# KeypadCapacitive.net
KiCad netlist of a schematic drawn in Altium Designer
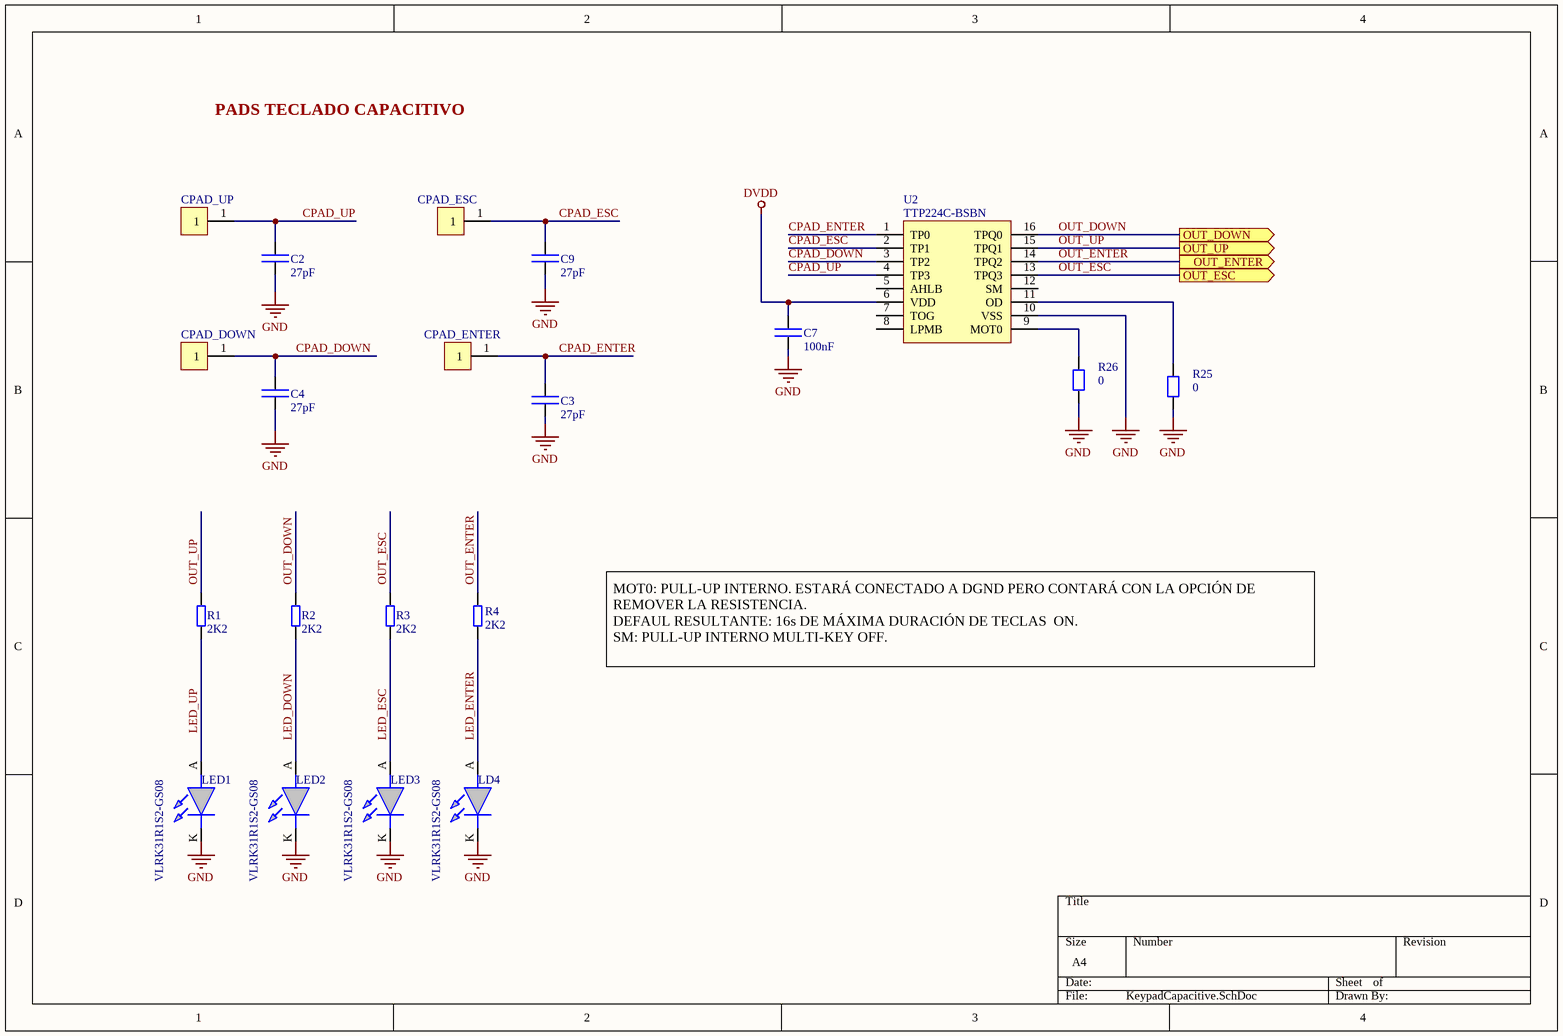
[diagram p0: KeypadCapacitive.SchDoc]

(export (version "E")
  (design (tool "Eeschema 10.0.6"))
  (components
    (comp (ref "C2")
      (value "27pF")
      (footprint "CAP_SM0603_YAGEOCC2_N")
      (description "CAP 27pF SM0603 NPO 50V YAGEO CC2")
      (fields
        (field (name "MANUFACTURER") "Yageo")
        (field (name "MANUFACTURER PART NUMBER") "CC0603JRNPO9BN270")
      )
      (libsource (lib "yageo") (part "CC0603JRNPO9BN270"))
    )
    (comp (ref "C3")
      (value "27pF")
      (footprint "CAP_SM0603_YAGEOCC2_N")
      (description "CAP 27pF SM0603 NPO 50V YAGEO CC2")
      (fields
        (field (name "MANUFACTURER") "Yageo")
        (field (name "MANUFACTURER PART NUMBER") "CC0603JRNPO9BN270")
      )
      (libsource (lib "yageo") (part "CC0603JRNPO9BN270"))
    )
    (comp (ref "C4")
      (value "27pF")
      (footprint "CAP_SM0603_YAGEOCC2_N")
      (description "CAP 27pF SM0603 NPO 50V YAGEO CC2")
      (fields
        (field (name "MANUFACTURER") "Yageo")
        (field (name "MANUFACTURER PART NUMBER") "CC0603JRNPO9BN270")
      )
      (libsource (lib "yageo") (part "CC0603JRNPO9BN270"))
    )
    (comp (ref "C7")
      (value "100nF")
      (footprint "CAP_SM0603_YAGEOCC2_N")
      (description "CAP 100nF SM0603 X7R 50V YAGEO CC2")
      (fields
        (field (name "MANUFACTURER") "Yageo")
        (field (name "MANUFACTURER PART NUMBER") "CC0603KRX7R9BB104")
      )
      (libsource (lib "yageo") (part "CC0603KRX7R9BB104"))
    )
    (comp (ref "C9")
      (value "27pF")
      (footprint "CAP_SM0603_YAGEOCC2_N")
      (description "CAP 27pF SM0603 NPO 50V YAGEO CC2")
      (fields
        (field (name "MANUFACTURER") "Yageo")
        (field (name "MANUFACTURER PART NUMBER") "CC0603JRNPO9BN270")
      )
      (libsource (lib "yageo") (part "CC0603JRNPO9BN270"))
    )
    (comp (ref "CPAD_DOWN")
      (value "DOWN")
      (footprint "CAPACITIVE_PAD_12MM")
      (fields (field (name "CHN-MANUFACTURER PARTNUMBER") "H146"))
      (libsource (lib "flowmeet") (part "CAPACITIVE_PAD_12MM"))
    )
    (comp (ref "CPAD_ENTER")
      (value "ENTER")
      (footprint "CAPACITIVE_PAD_12MM")
      (fields (field (name "CHN-MANUFACTURER PARTNUMBER") "H146"))
      (libsource (lib "flowmeet") (part "CAPACITIVE_PAD_12MM"))
    )
    (comp (ref "CPAD_ESC")
      (value "ESC")
      (footprint "CAPACITIVE_PAD_12MM")
      (fields (field (name "CHN-MANUFACTURER PARTNUMBER") "H146"))
      (libsource (lib "flowmeet") (part "CAPACITIVE_PAD_12MM"))
    )
    (comp (ref "CPAD_UP")
      (value "UP")
      (footprint "CAPACITIVE_PAD_12MM")
      (fields (field (name "CHN-MANUFACTURER PARTNUMBER") "H146"))
      (libsource (lib "flowmeet") (part "CAPACITIVE_PAD_12MM"))
    )
    (comp (ref "LD4")
      (value "VLRK31R1S2-GS08")
      (footprint "VLRK31R1S2GS08")
      (description "Red 630nm LED Indication - Discrete 2.1V 2-SMD, Z-Bend")
      (fields (field (name "MANUFACTURER") "Vishay"))
      (libsource (lib "flowmeet") (part "VLRK31R1S2-GS08"))
    )
    (comp (ref "LED1")
      (value "VLRK31R1S2-GS08")
      (footprint "VLRK31R1S2GS08")
      (description "Red 630nm LED Indication - Discrete 2.1V 2-SMD, Z-Bend")
      (fields (field (name "MANUFACTURER") "Vishay"))
      (libsource (lib "flowmeet") (part "VLRK31R1S2-GS08"))
    )
    (comp (ref "LED2")
      (value "VLRK31R1S2-GS08")
      (footprint "VLRK31R1S2GS08")
      (description "Red 630nm LED Indication - Discrete 2.1V 2-SMD, Z-Bend")
      (fields (field (name "MANUFACTURER") "Vishay"))
      (libsource (lib "flowmeet") (part "VLRK31R1S2-GS08"))
    )
    (comp (ref "LED3")
      (value "VLRK31R1S2-GS08")
      (footprint "VLRK31R1S2GS08")
      (description "Red 630nm LED Indication - Discrete 2.1V 2-SMD, Z-Bend")
      (fields (field (name "MANUFACTURER") "Vishay"))
      (libsource (lib "flowmeet") (part "VLRK31R1S2-GS08"))
    )
    (comp (ref "R1")
      (value "2K2")
      (footprint "RES_SM0603_YAGEORC_N")
      (description "RES 2K2 SM0603 YAGEO RC_L")
      (fields
        (field (name "MANUFACTURER") "Yageo")
        (field (name "MANUFACTURER PART NUMBER") "RC0603FR-072K2L")
      )
      (libsource (lib "yageo") (part "RC0603FR-072K2L"))
    )
    (comp (ref "R2")
      (value "2K2")
      (footprint "RES_SM0603_YAGEORC_N")
      (description "RES 2K2 SM0603 YAGEO RC_L")
      (fields
        (field (name "MANUFACTURER") "Yageo")
        (field (name "MANUFACTURER PART NUMBER") "RC0603FR-072K2L")
      )
      (libsource (lib "yageo") (part "RC0603FR-072K2L"))
    )
    (comp (ref "R3")
      (value "2K2")
      (footprint "RES_SM0603_YAGEORC_N")
      (description "RES 2K2 SM0603 YAGEO RC_L")
      (fields
        (field (name "MANUFACTURER") "Yageo")
        (field (name "MANUFACTURER PART NUMBER") "RC0603FR-072K2L")
      )
      (libsource (lib "yageo") (part "RC0603FR-072K2L"))
    )
    (comp (ref "R4")
      (value "2K2")
      (footprint "RES_SM0603_YAGEORC_N")
      (description "RES 2K2 SM0603 YAGEO RC_L")
      (fields
        (field (name "MANUFACTURER") "Yageo")
        (field (name "MANUFACTURER PART NUMBER") "RC0603FR-072K2L")
      )
      (libsource (lib "yageo") (part "RC0603FR-072K2L"))
    )
    (comp (ref "R25")
      (value "0")
      (footprint "RES_SM0603_YAGEORC_N")
      (description "RES 0 OHMS SM0603 YAGEO RC_L")
      (fields
        (field (name "MANUFACTURER") "Yageo")
        (field (name "MANUFACTURER PART NUMBER") "RC0603FR-070RL")
      )
      (libsource (lib "yageo") (part "RC0603FR-070RL"))
    )
    (comp (ref "R26")
      (value "0")
      (footprint "RES_SM0603_YAGEORC_N")
      (description "RES 0 OHMS SM0603 YAGEO RC_L")
      (fields
        (field (name "MANUFACTURER") "Yageo")
        (field (name "MANUFACTURER PART NUMBER") "RC0603FR-070RL")
      )
      (libsource (lib "yageo") (part "RC0603FR-070RL"))
    )
    (comp (ref "U2")
      (value "TTP224C-BSBN")
      (footprint "SSOP-16")
      (description "SSOP-16 Touch Screen Controllers ROHS")
      (fields
        (field (name "MANUFACTURER") "Tontek Design Tech")
        (field (name "VENDOR PART NUMBER") "C2890350")
      )
      (libsource (lib "flowmeet") (part "TTP224C-BSBN"))
    )
  )
  (nets
    (net (code "1") (name "/CPAD_DOWN") (class "Default")
      (node (ref "C4") (pin "2") (pintype "passive"))
      (node (ref "CPAD_DOWN") (pin "1") (pinfunction "1_1") (pintype "passive"))
      (node (ref "U2") (pin "3") (pinfunction "TP2_3") (pintype "passive"))
    )
    (net (code "2") (name "/CPAD_ENTER") (class "Default")
      (node (ref "C3") (pin "2") (pintype "passive"))
      (node (ref "CPAD_ENTER") (pin "1") (pinfunction "1_1") (pintype "passive"))
      (node (ref "U2") (pin "1") (pinfunction "TP0_1") (pintype "passive"))
    )
    (net (code "3") (name "/CPAD_ESC") (class "Default")
      (node (ref "C9") (pin "2") (pintype "passive"))
      (node (ref "CPAD_ESC") (pin "1") (pinfunction "1_1") (pintype "passive"))
      (node (ref "U2") (pin "2") (pinfunction "TP1_2") (pintype "passive"))
    )
    (net (code "4") (name "/CPAD_UP") (class "Default")
      (node (ref "C2") (pin "2") (pintype "passive"))
      (node (ref "CPAD_UP") (pin "1") (pinfunction "1_1") (pintype "passive"))
      (node (ref "U2") (pin "4") (pinfunction "TP3_4") (pintype "passive"))
    )
    (net (code "5") (name "/LED_DOWN") (class "Default")
      (node (ref "LED2") (pin "A") (pinfunction "A_A") (pintype "passive"))
      (node (ref "R2") (pin "1") (pintype "passive"))
    )
    (net (code "6") (name "/LED_ENTER") (class "Default")
      (node (ref "LD4") (pin "A") (pinfunction "A_A") (pintype "passive"))
      (node (ref "R4") (pin "1") (pintype "passive"))
    )
    (net (code "7") (name "/LED_ESC") (class "Default")
      (node (ref "LED3") (pin "A") (pinfunction "A_A") (pintype "passive"))
      (node (ref "R3") (pin "1") (pintype "passive"))
    )
    (net (code "8") (name "/LED_UP") (class "Default")
      (node (ref "LED1") (pin "A") (pinfunction "A_A") (pintype "passive"))
      (node (ref "R1") (pin "1") (pintype "passive"))
    )
    (net (code "9") (name "/OUT_DOWN") (class "Default")
      (node (ref "R2") (pin "2") (pintype "passive"))
      (node (ref "U2") (pin "16") (pinfunction "TPQ0_16") (pintype "passive"))
    )
    (net (code "10") (name "/OUT_ENTER") (class "Default")
      (node (ref "R4") (pin "2") (pintype "passive"))
      (node (ref "U2") (pin "14") (pinfunction "TPQ2_14") (pintype "passive"))
    )
    (net (code "11") (name "/OUT_ESC") (class "Default")
      (node (ref "R3") (pin "2") (pintype "passive"))
      (node (ref "U2") (pin "13") (pinfunction "TPQ3_13") (pintype "passive"))
    )
    (net (code "12") (name "/OUT_UP") (class "Default")
      (node (ref "R1") (pin "2") (pintype "passive"))
      (node (ref "U2") (pin "15") (pinfunction "TPQ1_15") (pintype "passive"))
    )
    (net (code "13") (name "DVDD") (class "Default")
      (node (ref "C7") (pin "2") (pintype "passive"))
      (node (ref "U2") (pin "6") (pinfunction "VDD_6") (pintype "passive"))
    )
    (net (code "14") (name "GND") (class "Default")
      (node (ref "C2") (pin "1") (pintype "passive"))
      (node (ref "C3") (pin "1") (pintype "passive"))
      (node (ref "C4") (pin "1") (pintype "passive"))
      (node (ref "C7") (pin "1") (pintype "passive"))
      (node (ref "C9") (pin "1") (pintype "passive"))
      (node (ref "LD4") (pin "K") (pinfunction "K_K") (pintype "passive"))
      (node (ref "LED1") (pin "K") (pinfunction "K_K") (pintype "passive"))
      (node (ref "LED2") (pin "K") (pinfunction "K_K") (pintype "passive"))
      (node (ref "LED3") (pin "K") (pinfunction "K_K") (pintype "passive"))
      (node (ref "R25") (pin "1") (pintype "passive"))
      (node (ref "R26") (pin "1") (pintype "passive"))
      (node (ref "U2") (pin "10") (pinfunction "VSS_10") (pintype "passive"))
    )
    (net (code "15") (name "Net-(U2-MOT0)") (class "Default")
      (node (ref "R26") (pin "2") (pintype "passive"))
      (node (ref "U2") (pin "9") (pinfunction "MOT0_9") (pintype "passive"))
    )
    (net (code "16") (name "Net-(U2-OD)") (class "Default")
      (node (ref "R25") (pin "2") (pintype "passive"))
      (node (ref "U2") (pin "11") (pinfunction "OD_11") (pintype "passive"))
    )
    (net (code "17") (name "unconnected-(U2-AHLB-Pad5)") (class "Default")
      (node (ref "U2") (pin "5") (pinfunction "AHLB_5") (pintype "passive"))
    )
    (net (code "18") (name "unconnected-(U2-LPMB-Pad8)") (class "Default")
      (node (ref "U2") (pin "8") (pinfunction "LPMB_8") (pintype "passive"))
    )
    (net (code "19") (name "unconnected-(U2-SM-Pad12)") (class "Default")
      (node (ref "U2") (pin "12") (pinfunction "SM_12") (pintype "passive"))
    )
    (net (code "20") (name "unconnected-(U2-TOG-Pad7)") (class "Default")
      (node (ref "U2") (pin "7") (pinfunction "TOG_7") (pintype "passive"))
    )
  )
)
